# stwin_inclinometer.net
KiCad netlist of a schematic drawn in EAGLE
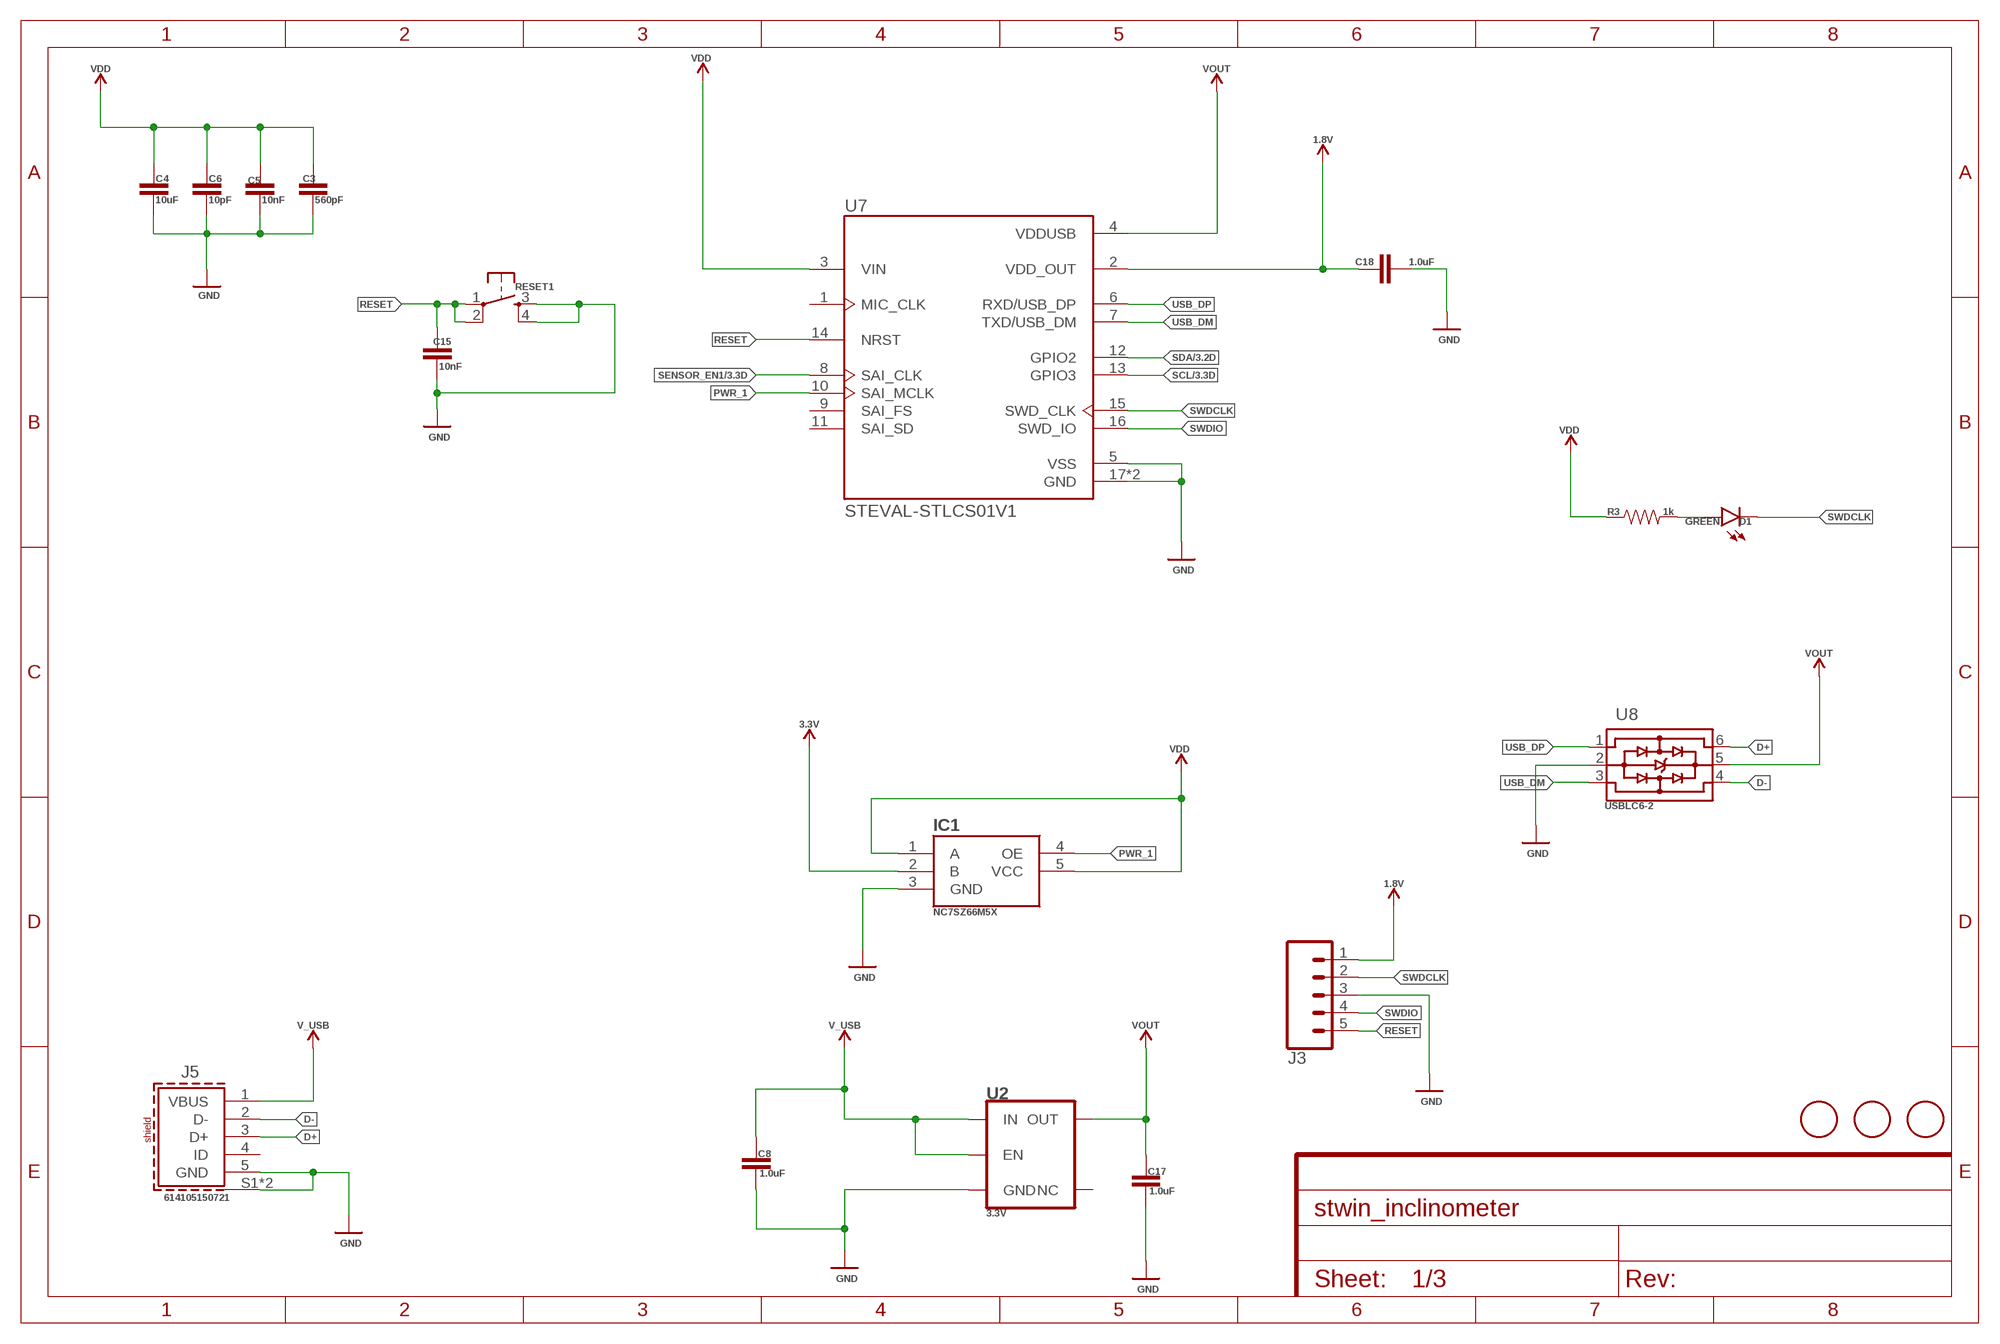
[diagram p0: schematic, sheet 1]
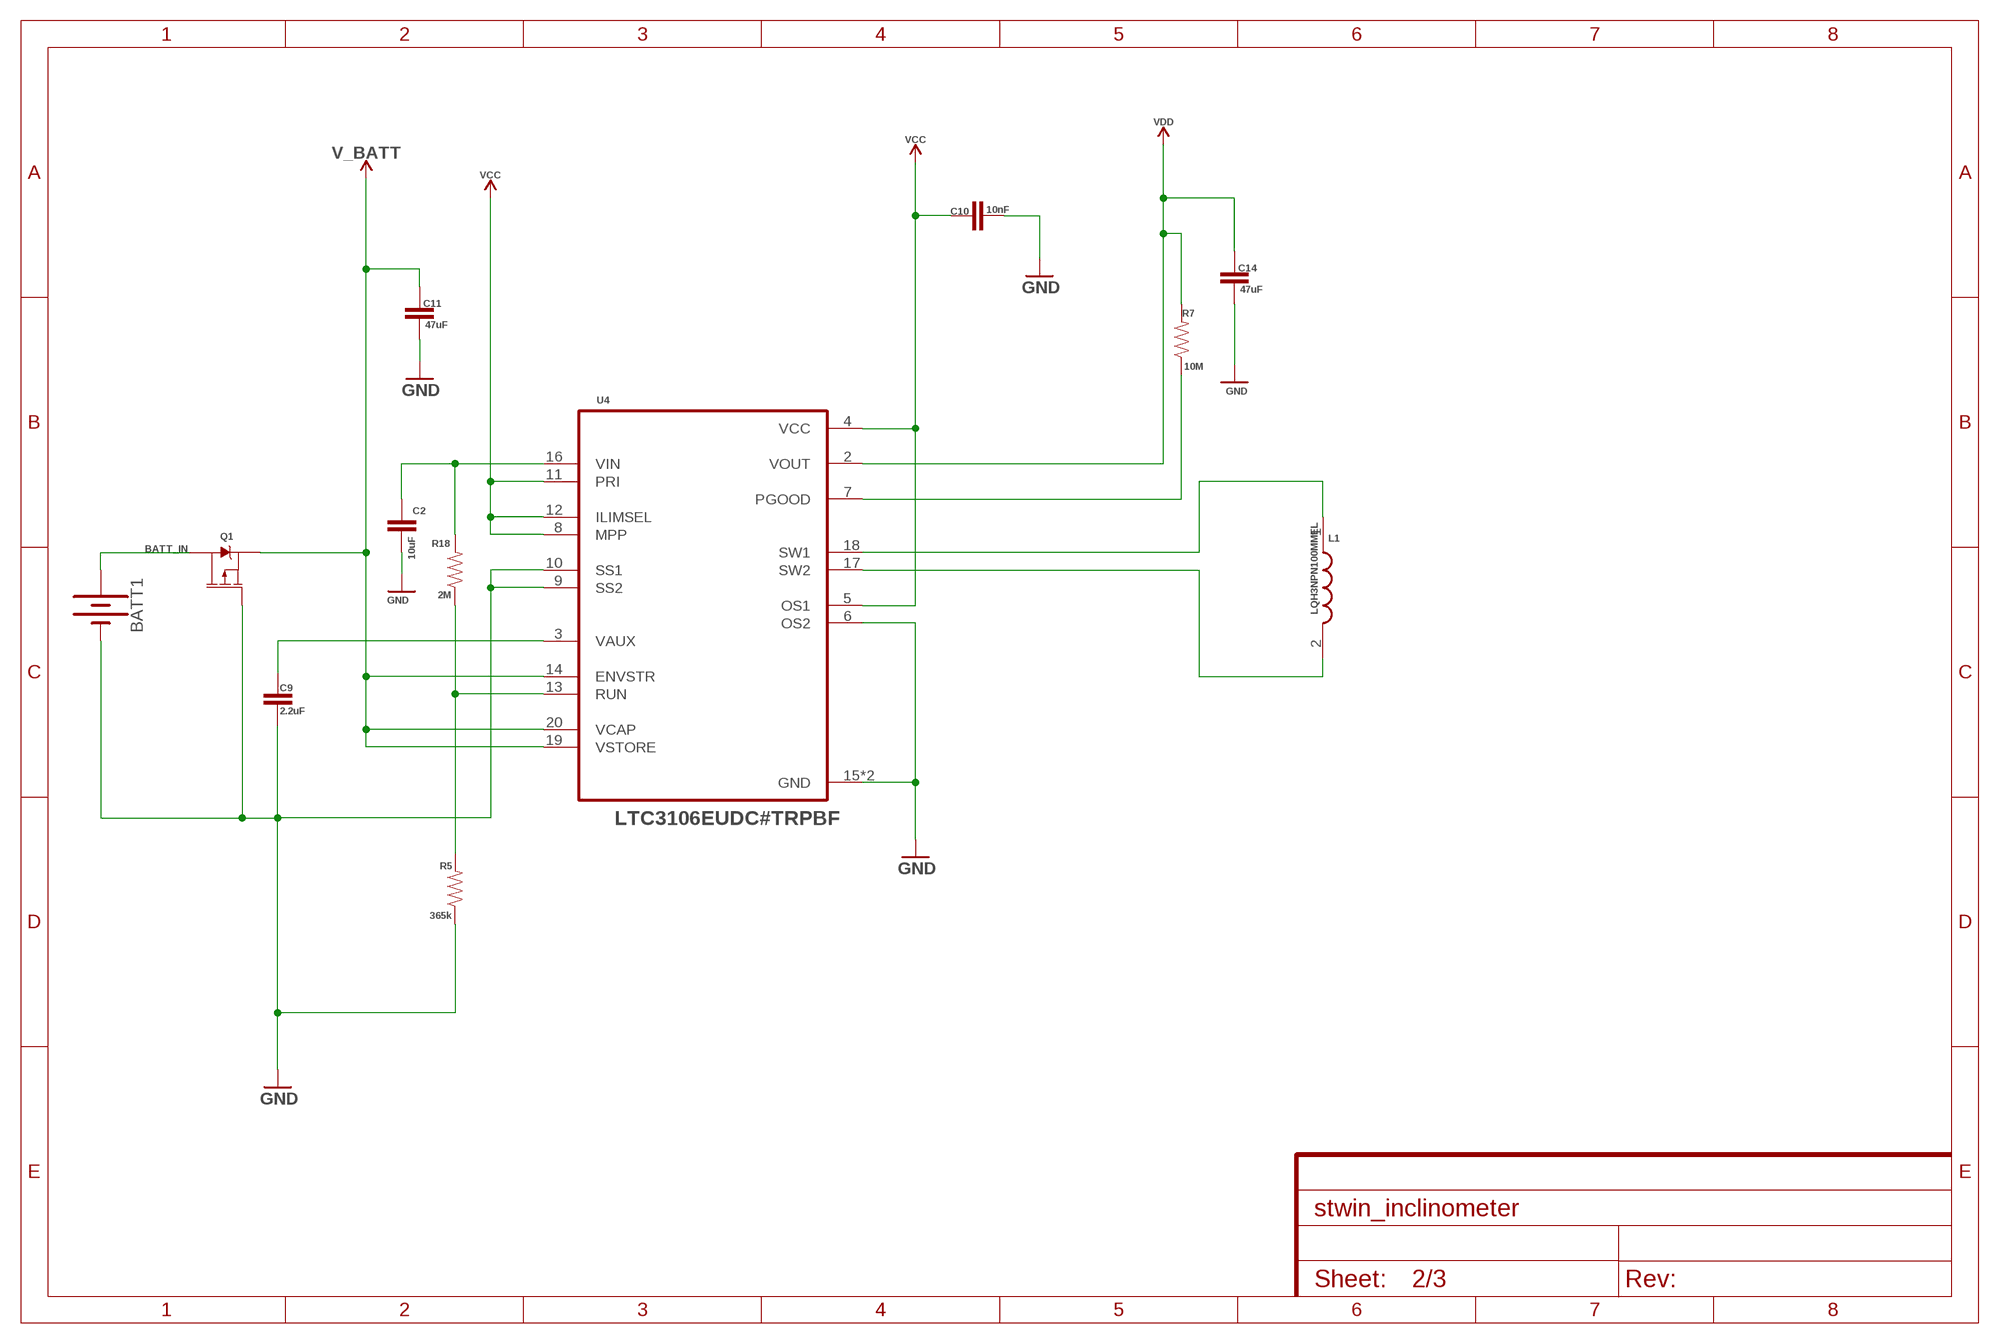
[diagram p1: schematic, sheet 2]
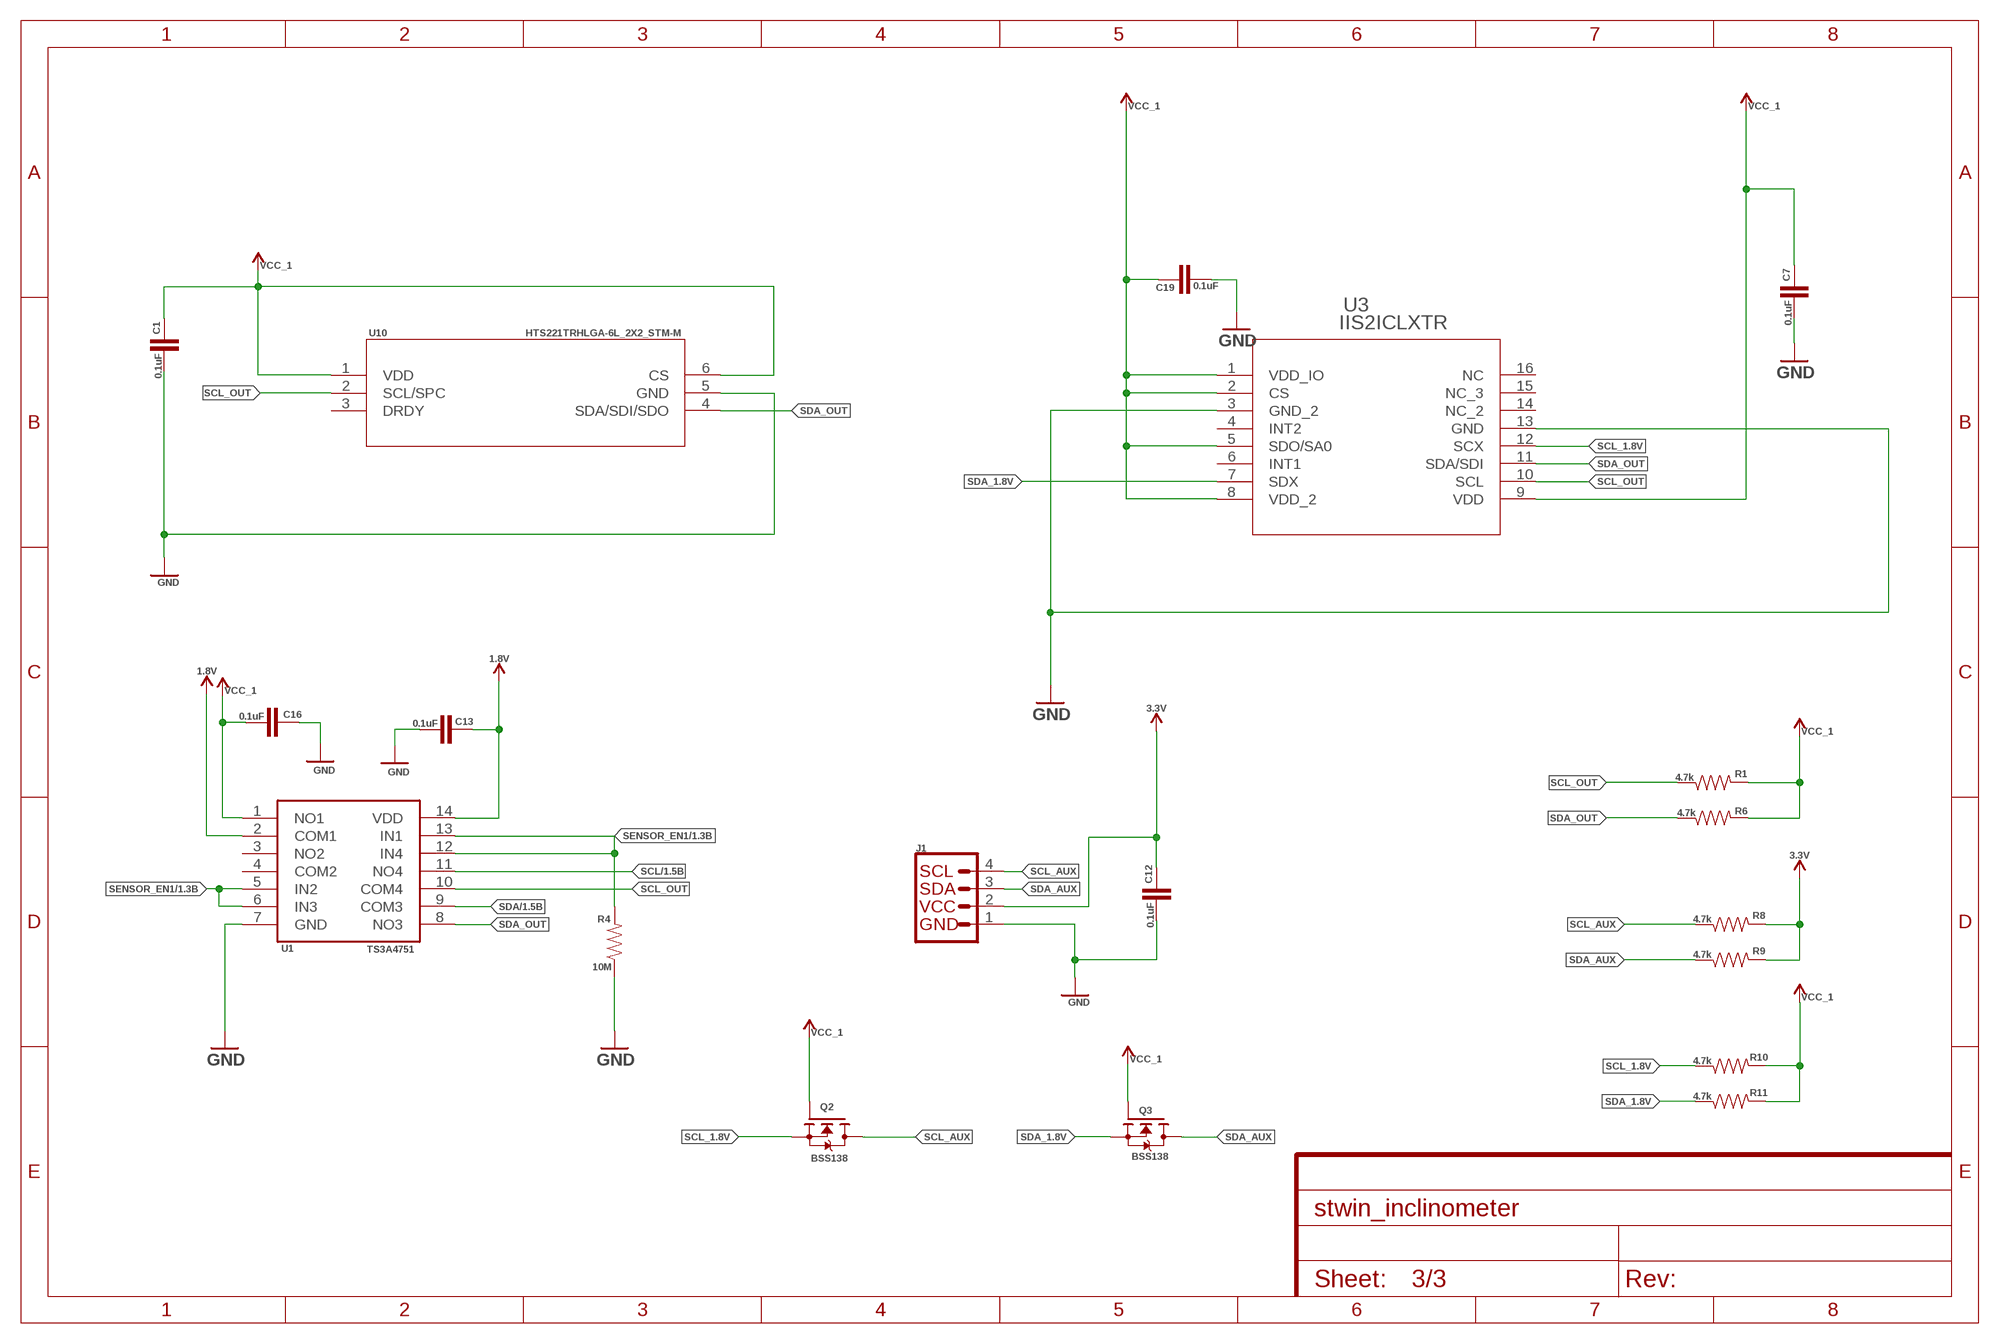
[diagram p2: schematic, sheet 3]

(export (version "E")
  (design (tool "Eeschema 10.0.6"))
  (components
    (comp (ref "C1")
      (value "0.1uF")
      (footprint "eagle-import:0603")
      (libsource (lib "eagle-import") (part "0.1UF-0603-25V-(+80/-20%)"))
    )
    (comp (ref "C7")
      (value "0.1uF")
      (footprint "eagle-import:0603")
      (libsource (lib "eagle-import") (part "0.1UF-0603-25V-(+80/-20%)"))
    )
    (comp (ref "C12")
      (value "0.1uF")
      (footprint "eagle-import:0603")
      (libsource (lib "eagle-import") (part "0.1UF-0603-25V-(+80/-20%)"))
    )
    (comp (ref "C13")
      (value "0.1uF")
      (footprint "eagle-import:0603")
      (libsource (lib "eagle-import") (part "0.1UF-0603-25V-(+80/-20%)"))
    )
    (comp (ref "C16")
      (value "0.1uF")
      (footprint "eagle-import:0603")
      (libsource (lib "eagle-import") (part "0.1UF-0603-25V-(+80/-20%)"))
    )
    (comp (ref "C19")
      (value "0.1uF")
      (footprint "eagle-import:0603")
      (libsource (lib "eagle-import") (part "0.1UF-0603-25V-(+80/-20%)"))
    )
    (comp (ref "J1")
      (value "I2C_STANDARD")
      (footprint "eagle-import:1X04")
      (libsource (lib "eagle-import") (part "I2C_STANDARD"))
    )
    (comp (ref "Q2")
      (value "BSS138")
      (footprint "eagle-import:SOT95P240X111-3N")
      (fields (field (name "MF") "ON Semiconductor"))
      (libsource (lib "eagle-import") (part "BSS138"))
    )
    (comp (ref "Q3")
      (value "BSS138")
      (footprint "eagle-import:SOT95P240X111-3N")
      (fields (field (name "MF") "ON Semiconductor"))
      (libsource (lib "eagle-import") (part "BSS138"))
    )
    (comp (ref "R1")
      (value "4.7k")
      (footprint "eagle-import:0603")
      (libsource (lib "eagle-import") (part "4.7KOHM-0603-1/10W-1%"))
    )
    (comp (ref "R4")
      (value "10M")
      (footprint "eagle-import:0603")
      (libsource (lib "eagle-import") (part "10MOHM-0603-1/10W-5%"))
    )
    (comp (ref "R6")
      (value "4.7k")
      (footprint "eagle-import:0603")
      (libsource (lib "eagle-import") (part "4.7KOHM-0603-1/10W-1%"))
    )
    (comp (ref "R8")
      (value "4.7k")
      (footprint "eagle-import:0603")
      (libsource (lib "eagle-import") (part "4.7KOHM-0603-1/10W-1%"))
    )
    (comp (ref "R9")
      (value "4.7k")
      (footprint "eagle-import:0603")
      (libsource (lib "eagle-import") (part "4.7KOHM-0603-1/10W-1%"))
    )
    (comp (ref "R10")
      (value "4.7k")
      (footprint "eagle-import:0603")
      (libsource (lib "eagle-import") (part "4.7KOHM-0603-1/10W-1%"))
    )
    (comp (ref "R11")
      (value "4.7k")
      (footprint "eagle-import:0603")
      (libsource (lib "eagle-import") (part "4.7KOHM-0603-1/10W-1%"))
    )
    (comp (ref "U1")
      (value "TS3A4751")
      (footprint "eagle-import:14_PIN")
      (fields (field (name "MF") "Texas Instruments"))
      (libsource (lib "eagle-import") (part "TS3A4751"))
    )
    (comp (ref "U3")
      (value "IIS2ICLXTR")
      (footprint "eagle-import:QFN_ICLX_STM")
      (fields (field (name "COPYRIGHT") "Copyright (C) 2018 Accelerated Designs. All rights reserved"))
      (libsource (lib "eagle-import") (part "IIS2ICLXTR"))
    )
    (comp (ref "U10")
      (value "HTS221TRHLGA-6L_2X2_STM-M")
      (footprint "eagle-import:HLGA-6L_2X2_STM-M")
      (fields
        (field (name "MANUFACTURER_PART_NUMBER") "HTS221TR")
        (field (name "COPYRIGHT") "Copyright (C) 2018 Accelerated Designs. All rights reserved")
      )
      (libsource (lib "eagle-import") (part "HTS221TRHLGA-6L_2X2_STM-M"))
    )
    (comp (ref "C3")
      (value "560pF")
      (footprint "eagle-import:0603")
      (libsource (lib "eagle-import") (part "560PF-0603-50V-5%"))
    )
    (comp (ref "C4")
      (value "10uF")
      (footprint "eagle-import:0603")
      (libsource (lib "eagle-import") (part "10UF-0603-6.3V-20%"))
    )
    (comp (ref "C5")
      (value "10nF")
      (footprint "eagle-import:0603")
      (libsource (lib "eagle-import") (part "10NF-0603-50V-10%"))
    )
    (comp (ref "C6")
      (value "10pF")
      (footprint "eagle-import:0603")
      (libsource (lib "eagle-import") (part "10PF-0603-50V-5%"))
    )
    (comp (ref "C8")
      (value "1.0uF")
      (footprint "eagle-import:0603")
      (libsource (lib "eagle-import") (part "1.0UF-0603-16V-10%"))
    )
    (comp (ref "C15")
      (value "10nF")
      (footprint "eagle-import:0603")
      (libsource (lib "eagle-import") (part "10NF-0603-50V-10%"))
    )
    (comp (ref "C17")
      (value "1.0uF")
      (footprint "eagle-import:0603")
      (libsource (lib "eagle-import") (part "1.0UF-0603-16V-10%"))
    )
    (comp (ref "C18")
      (value "1.0uF")
      (footprint "eagle-import:0603")
      (libsource (lib "eagle-import") (part "1.0UF-0603-16V-10%"))
    )
    (comp (ref "D1")
      (value "GREEN")
      (footprint "eagle-import:LED-0603")
      (libsource (lib "eagle-import") (part "LED-GREEN0603"))
    )
    (comp (ref "IC1")
      (value "NC7SZ66M5X")
      (footprint "eagle-import:SOT95P280X145-5N")
      (fields (field (name "MOUSER_PART_NUMBER") "512-NC7SZ66M5X"))
      (libsource (lib "eagle-import") (part "NC7SZ66M5X"))
    )
    (comp (ref "J3")
      (value "CONN_05LOCK_LONGPADS")
      (footprint "eagle-import:1X05_LOCK_LONGPADS")
      (libsource (lib "eagle-import") (part "CONN_05LOCK_LONGPADS"))
    )
    (comp (ref "J5")
      (value "614105150721")
      (footprint "eagle-import:614105150721")
      (fields (field (name "MF") "Wurth Electronics"))
      (libsource (lib "eagle-import") (part "614105150721"))
    )
    (comp (ref "R3")
      (value "1k")
      (footprint "eagle-import:0603")
      (libsource (lib "eagle-import") (part "1KOHM-0603-1/10W-1%"))
    )
    (comp (ref "RESET1")
      (value "MOMENTARY-SWITCH-SPST-2-SMD-4.6X2.8MM")
      (footprint "eagle-import:TACTILE_SWITCH_SMD_4.6X2.8MM")
      (libsource (lib "eagle-import") (part "MOMENTARY-SWITCH-SPST-2-SMD-4.6X2.8MM"))
    )
    (comp (ref "U$5")
      (value "FIDUCIAL")
      (footprint "eagle-import:FIDUCIAL_1MM")
      (libsource (lib "eagle-import") (part "FIDUCIAL"))
    )
    (comp (ref "U$6")
      (value "FIDUCIAL")
      (footprint "eagle-import:FIDUCIAL_1MM")
      (libsource (lib "eagle-import") (part "FIDUCIAL"))
    )
    (comp (ref "U$7")
      (value "FIDUCIAL")
      (footprint "eagle-import:FIDUCIAL_1MM")
      (libsource (lib "eagle-import") (part "FIDUCIAL"))
    )
    (comp (ref "U2")
      (value "3.3V")
      (footprint "eagle-import:SOT23-5")
      (libsource (lib "eagle-import") (part "V_REG_AP2112K-3.3V"))
    )
    (comp (ref "U7")
      (value "STEVAL-STLCS01V1")
      (footprint "eagle-import:XDCR_STEVAL-STLCS01V1")
      (fields (field (name "MF") "STMicroelectronics"))
      (libsource (lib "eagle-import") (part "STEVAL-STLCS01V1"))
    )
    (comp (ref "U8")
      (value "USBLC6-2")
      (footprint "eagle-import:USBLC6-2P6")
      (fields (field (name "MF") "STMicroelectronics"))
      (libsource (lib "eagle-import") (part "USBLC6-2"))
    )
    (comp (ref "BATT1")
      (value "KEYSTONE_54KEYSTONE_2")
      (footprint "eagle-import:KEYSTONE_V2")
      (libsource (lib "eagle-import") (part "KEYSTONE_54KEYSTONE_2"))
    )
    (comp (ref "C2")
      (value "10uF")
      (footprint "eagle-import:0603")
      (libsource (lib "eagle-import") (part "10UF-0603-6.3V-20%"))
    )
    (comp (ref "C9")
      (value "2.2uF")
      (footprint "eagle-import:0603")
      (libsource (lib "eagle-import") (part "2.2UF-0603-10V-20%"))
    )
    (comp (ref "C10")
      (value "10nF")
      (footprint "eagle-import:0603")
      (libsource (lib "eagle-import") (part "10NF-0603-50V-10%"))
    )
    (comp (ref "C11")
      (value "47uF")
      (footprint "eagle-import:0603")
      (libsource (lib "eagle-import") (part "4.7UF0603"))
    )
    (comp (ref "C14")
      (value "47uF")
      (footprint "eagle-import:0603")
      (libsource (lib "eagle-import") (part "4.7UF0603"))
    )
    (comp (ref "L1")
      (value "LQH3NPN100MMEL")
      (footprint "eagle-import:INDPM3030X150N")
      (fields (field (name "MOUSER_PART_NUMBER") "81-LQH3NPN100MMEL"))
      (libsource (lib "eagle-import") (part "LQH3NPN100MMEL"))
    )
    (comp (ref "Q1")
      (value "2.5A/30V/105mΩ")
      (footprint "eagle-import:SOT23-3")
      (libsource (lib "eagle-import") (part "MOSFET_PCH-DMG2307L"))
    )
    (comp (ref "R5")
      (value "365k")
      (footprint "eagle-import:0603")
      (libsource (lib "eagle-import") (part "348KOHM-0603-1/10W-1%"))
    )
    (comp (ref "R7")
      (value "10M")
      (footprint "eagle-import:0603")
      (libsource (lib "eagle-import") (part "10MOHM-0603-1/10W-5%"))
    )
    (comp (ref "R18")
      (value "2M")
      (footprint "eagle-import:0603")
      (libsource (lib "eagle-import") (part "1MOHM-0603-1/4W-5%"))
    )
    (comp (ref "U4")
      (value "LTC3106EUDC#TRPBF")
      (footprint "eagle-import:QFN50P400X300X80-21N")
      (fields (field (name "MF") "Linear Technology/Analog"))
      (libsource (lib "eagle-import") (part "LTC3106EUDC#TRPBF"))
    )
  )
  (nets
    (net (code "1") (name "1.8V") (class "Default")
      (node (ref "C13") (pin "1") (pinfunction "1_1") (pintype "passive"))
      (node (ref "C18") (pin "1") (pinfunction "1_1") (pintype "passive"))
      (node (ref "J3") (pin "1") (pinfunction "1_1") (pintype "passive"))
      (node (ref "U1") (pin "14") (pinfunction "VDD_14") (pintype "bidirectional"))
      (node (ref "U1") (pin "2") (pinfunction "COM1_2") (pintype "bidirectional"))
      (node (ref "U7") (pin "2") (pinfunction "VDD_OUT_2") (pintype "output"))
    )
    (net (code "2") (name "3.3V") (class "Default")
      (node (ref "C12") (pin "1") (pinfunction "1_1") (pintype "passive"))
      (node (ref "IC1") (pin "2") (pinfunction "B_2") (pintype "bidirectional"))
      (node (ref "J1") (pin "2") (pinfunction "2_2") (pintype "power_in"))
      (node (ref "R8") (pin "2") (pinfunction "2_2") (pintype "passive"))
      (node (ref "R9") (pin "2") (pinfunction "2_2") (pintype "passive"))
    )
    (net (code "3") (name "BATT_IN") (class "Default")
      (node (ref "BATT1") (pin "P$1") (pinfunction "+_P$1") (pintype "power_in"))
      (node (ref "BATT1") (pin "P$2") (pinfunction "+_P$2") (pintype "power_in"))
      (node (ref "BATT1") (pin "P$3") (pinfunction "+_P$3") (pintype "power_in"))
      (node (ref "Q1") (pin "3") (pinfunction "D_3") (pintype "bidirectional"))
    )
    (net (code "4") (name "D+") (class "Default")
      (node (ref "J5") (pin "3") (pinfunction "D+_3") (pintype "passive"))
      (node (ref "U8") (pin "6") (pinfunction "6_6") (pintype "bidirectional"))
    )
    (net (code "5") (name "D-") (class "Default")
      (node (ref "J5") (pin "2") (pinfunction "D-_2") (pintype "passive"))
      (node (ref "U8") (pin "4") (pinfunction "4_4") (pintype "bidirectional"))
    )
    (net (code "6") (name "GND") (class "Default")
      (node (ref "BATT1") (pin "P$4") (pinfunction "-_P$4") (pintype "power_in"))
      (node (ref "BATT1") (pin "P$5") (pinfunction "-_P$5") (pintype "power_in"))
      (node (ref "BATT1") (pin "P$6") (pinfunction "-_P$6") (pintype "power_in"))
      (node (ref "C1") (pin "2") (pinfunction "2_2") (pintype "passive"))
      (node (ref "C10") (pin "2") (pinfunction "2_2") (pintype "passive"))
      (node (ref "C11") (pin "2") (pinfunction "2_2") (pintype "passive"))
      (node (ref "C12") (pin "2") (pinfunction "2_2") (pintype "passive"))
      (node (ref "C13") (pin "2") (pinfunction "2_2") (pintype "passive"))
      (node (ref "C14") (pin "2") (pinfunction "2_2") (pintype "passive"))
      (node (ref "C15") (pin "1") (pinfunction "1_1") (pintype "passive"))
      (node (ref "C16") (pin "1") (pinfunction "1_1") (pintype "passive"))
      (node (ref "C17") (pin "2") (pinfunction "2_2") (pintype "passive"))
      (node (ref "C18") (pin "2") (pinfunction "2_2") (pintype "passive"))
      (node (ref "C19") (pin "2") (pinfunction "2_2") (pintype "passive"))
      (node (ref "C2") (pin "2") (pinfunction "2_2") (pintype "passive"))
      (node (ref "C3") (pin "1") (pinfunction "1_1") (pintype "passive"))
      (node (ref "C4") (pin "1") (pinfunction "1_1") (pintype "passive"))
      (node (ref "C5") (pin "1") (pinfunction "1_1") (pintype "passive"))
      (node (ref "C6") (pin "1") (pinfunction "1_1") (pintype "passive"))
      (node (ref "C7") (pin "2") (pinfunction "2_2") (pintype "passive"))
      (node (ref "C8") (pin "2") (pinfunction "2_2") (pintype "passive"))
      (node (ref "C9") (pin "2") (pinfunction "2_2") (pintype "passive"))
      (node (ref "IC1") (pin "3") (pinfunction "GND_3") (pintype "power_in"))
      (node (ref "J1") (pin "1") (pinfunction "1_1") (pintype "power_in"))
      (node (ref "J3") (pin "3") (pinfunction "3_3") (pintype "passive"))
      (node (ref "J5") (pin "5") (pinfunction "GND_5") (pintype "passive"))
      (node (ref "J5") (pin "S1") (pinfunction "SHIELD_S1") (pintype "passive"))
      (node (ref "J5") (pin "S2") (pinfunction "SHIELD_S2") (pintype "passive"))
      (node (ref "Q1") (pin "1") (pinfunction "G_1") (pintype "bidirectional"))
      (node (ref "R4") (pin "1") (pinfunction "1_1") (pintype "passive"))
      (node (ref "R5") (pin "1") (pinfunction "1_1") (pintype "passive"))
      (node (ref "RESET1") (pin "3") (pinfunction "3_3") (pintype "passive"))
      (node (ref "RESET1") (pin "4") (pinfunction "4_4") (pintype "passive"))
      (node (ref "U1") (pin "7") (pinfunction "GND_7") (pintype "bidirectional"))
      (node (ref "U10") (pin "5") (pinfunction "GND_5") (pintype "passive"))
      (node (ref "U2") (pin "2") (pinfunction "GND_2") (pintype "input"))
      (node (ref "U3") (pin "13") (pinfunction "GND_13") (pintype "passive"))
      (node (ref "U3") (pin "3") (pinfunction "GND_2_3") (pintype "passive"))
      (node (ref "U4") (pin "10") (pinfunction "SS1_10") (pintype "input"))
      (node (ref "U4") (pin "15") (pinfunction "GND_15") (pintype "power_in"))
      (node (ref "U4") (pin "21") (pinfunction "GND_21") (pintype "power_in"))
      (node (ref "U4") (pin "6") (pinfunction "OS2_6") (pintype "input"))
      (node (ref "U4") (pin "9") (pinfunction "SS2_9") (pintype "input"))
      (node (ref "U7") (pin "17") (pinfunction "GND_17") (pintype "power_in"))
      (node (ref "U7") (pin "18") (pinfunction "GND_18") (pintype "power_in"))
      (node (ref "U7") (pin "5") (pinfunction "VSS_5") (pintype "power_in"))
      (node (ref "U8") (pin "2") (pinfunction "2_2") (pintype "power_in"))
    )
    (net (code "7") (name "Net-(D1-PadA)") (class "Default")
      (node (ref "D1") (pin "A") (pinfunction "A_A") (pintype "passive"))
      (node (ref "R3") (pin "2") (pinfunction "2_2") (pintype "passive"))
    )
    (net (code "8") (name "Net-(U4-PGOOD)") (class "Default")
      (node (ref "R7") (pin "1") (pinfunction "1_1") (pintype "passive"))
      (node (ref "U4") (pin "7") (pinfunction "PGOOD_7") (pintype "bidirectional"))
    )
    (net (code "9") (name "Net-(U4-RUN)") (class "Default")
      (node (ref "R18") (pin "1") (pinfunction "1_1") (pintype "passive"))
      (node (ref "R5") (pin "2") (pinfunction "2_2") (pintype "passive"))
      (node (ref "U4") (pin "13") (pinfunction "RUN_13") (pintype "input"))
    )
    (net (code "10") (name "Net-(U4-SW1)") (class "Default")
      (node (ref "L1") (pin "1") (pinfunction "1_1") (pintype "bidirectional"))
      (node (ref "U4") (pin "18") (pinfunction "SW1_18") (pintype "bidirectional"))
    )
    (net (code "11") (name "Net-(U4-SW2)") (class "Default")
      (node (ref "L1") (pin "2") (pinfunction "2_2") (pintype "bidirectional"))
      (node (ref "U4") (pin "17") (pinfunction "SW2_17") (pintype "bidirectional"))
    )
    (net (code "12") (name "Net-(U4-VAUX)") (class "Default")
      (node (ref "C9") (pin "1") (pinfunction "1_1") (pintype "passive"))
      (node (ref "U4") (pin "3") (pinfunction "VAUX_3") (pintype "bidirectional"))
    )
    (net (code "13") (name "Net-(U4-VIN)") (class "Default")
      (node (ref "C2") (pin "1") (pinfunction "1_1") (pintype "passive"))
      (node (ref "R18") (pin "2") (pinfunction "2_2") (pintype "passive"))
      (node (ref "U4") (pin "16") (pinfunction "VIN_16") (pintype "input"))
    )
    (net (code "14") (name "PWR_1") (class "Default")
      (node (ref "IC1") (pin "4") (pinfunction "OE_4") (pintype "input"))
      (node (ref "U7") (pin "10") (pinfunction "SAI_MCLK_10") (pintype "bidirectional"))
    )
    (net (code "15") (name "RESET") (class "Default")
      (node (ref "C15") (pin "2") (pinfunction "2_2") (pintype "passive"))
      (node (ref "J3") (pin "5") (pinfunction "5_5") (pintype "passive"))
      (node (ref "RESET1") (pin "1") (pinfunction "1_1") (pintype "passive"))
      (node (ref "RESET1") (pin "2") (pinfunction "2_2") (pintype "passive"))
      (node (ref "U7") (pin "14") (pinfunction "NRST_14") (pintype "input"))
    )
    (net (code "16") (name "SCL") (class "Default")
      (node (ref "U1") (pin "11") (pinfunction "NO4_11") (pintype "bidirectional"))
      (node (ref "U7") (pin "13") (pinfunction "GPIO3_13") (pintype "bidirectional"))
    )
    (net (code "17") (name "SCL_1.8V") (class "Default")
      (node (ref "Q2") (pin "2") (pinfunction "S_2") (pintype "passive"))
      (node (ref "R10") (pin "1") (pinfunction "1_1") (pintype "passive"))
      (node (ref "U3") (pin "12") (pinfunction "SCX_12") (pintype "passive"))
    )
    (net (code "18") (name "SCL_AUX") (class "Default")
      (node (ref "J1") (pin "4") (pinfunction "4_4") (pintype "passive"))
      (node (ref "Q2") (pin "3") (pinfunction "D_3") (pintype "passive"))
      (node (ref "R8") (pin "1") (pinfunction "1_1") (pintype "passive"))
    )
    (net (code "19") (name "SCL_OUT") (class "Default")
      (node (ref "R1") (pin "1") (pinfunction "1_1") (pintype "passive"))
      (node (ref "U1") (pin "10") (pinfunction "COM4_10") (pintype "bidirectional"))
      (node (ref "U10") (pin "2") (pinfunction "SCL/SPC_2") (pintype "passive"))
      (node (ref "U3") (pin "10") (pinfunction "SCL_10") (pintype "passive"))
    )
    (net (code "20") (name "SDA") (class "Default")
      (node (ref "U1") (pin "9") (pinfunction "COM3_9") (pintype "bidirectional"))
      (node (ref "U7") (pin "12") (pinfunction "GPIO2_12") (pintype "bidirectional"))
    )
    (net (code "21") (name "SDA_1.8V") (class "Default")
      (node (ref "Q3") (pin "2") (pinfunction "S_2") (pintype "passive"))
      (node (ref "R11") (pin "1") (pinfunction "1_1") (pintype "passive"))
      (node (ref "U3") (pin "7") (pinfunction "SDX_7") (pintype "passive"))
    )
    (net (code "22") (name "SDA_AUX") (class "Default")
      (node (ref "J1") (pin "3") (pinfunction "3_3") (pintype "passive"))
      (node (ref "Q3") (pin "3") (pinfunction "D_3") (pintype "passive"))
      (node (ref "R9") (pin "1") (pinfunction "1_1") (pintype "passive"))
    )
    (net (code "23") (name "SDA_OUT") (class "Default")
      (node (ref "R6") (pin "1") (pinfunction "1_1") (pintype "passive"))
      (node (ref "U1") (pin "8") (pinfunction "NO3_8") (pintype "bidirectional"))
      (node (ref "U10") (pin "4") (pinfunction "SDA/SDI/SDO_4") (pintype "passive"))
      (node (ref "U3") (pin "11") (pinfunction "SDA/SDI_11") (pintype "passive"))
    )
    (net (code "24") (name "SENSOR_EN1") (class "Default")
      (node (ref "R4") (pin "2") (pinfunction "2_2") (pintype "passive"))
      (node (ref "U1") (pin "12") (pinfunction "IN4_12") (pintype "bidirectional"))
      (node (ref "U1") (pin "13") (pinfunction "IN1_13") (pintype "bidirectional"))
      (node (ref "U1") (pin "5") (pinfunction "IN2_5") (pintype "bidirectional"))
      (node (ref "U1") (pin "6") (pinfunction "IN3_6") (pintype "bidirectional"))
      (node (ref "U7") (pin "8") (pinfunction "SAI_CLK_8") (pintype "bidirectional"))
    )
    (net (code "25") (name "SWDCLK") (class "Default")
      (node (ref "D1") (pin "C") (pinfunction "C_C") (pintype "passive"))
      (node (ref "J3") (pin "2") (pinfunction "2_2") (pintype "passive"))
      (node (ref "U7") (pin "15") (pinfunction "SWD_CLK_15") (pintype "bidirectional"))
    )
    (net (code "26") (name "SWDIO") (class "Default")
      (node (ref "J3") (pin "4") (pinfunction "4_4") (pintype "passive"))
      (node (ref "U7") (pin "16") (pinfunction "SWD_IO_16") (pintype "bidirectional"))
    )
    (net (code "27") (name "USB_DM") (class "Default")
      (node (ref "U7") (pin "7") (pinfunction "TXD/USB_DM_7") (pintype "bidirectional"))
      (node (ref "U8") (pin "3") (pinfunction "3_3") (pintype "bidirectional"))
    )
    (net (code "28") (name "USB_DP") (class "Default")
      (node (ref "U7") (pin "6") (pinfunction "RXD/USB_DP_6") (pintype "bidirectional"))
      (node (ref "U8") (pin "1") (pinfunction "1_1") (pintype "bidirectional"))
    )
    (net (code "29") (name "VCC") (class "Default")
      (node (ref "C10") (pin "1") (pinfunction "1_1") (pintype "passive"))
      (node (ref "U4") (pin "11") (pinfunction "PRI_11") (pintype "input"))
      (node (ref "U4") (pin "12") (pinfunction "ILIMSEL_12") (pintype "input"))
      (node (ref "U4") (pin "4") (pinfunction "VCC_4") (pintype "power_in"))
      (node (ref "U4") (pin "5") (pinfunction "OS1_5") (pintype "input"))
      (node (ref "U4") (pin "8") (pinfunction "MPP_8") (pintype "input"))
    )
    (net (code "30") (name "VCC_1") (class "Default")
      (node (ref "C1") (pin "1") (pinfunction "1_1") (pintype "passive"))
      (node (ref "C16") (pin "2") (pinfunction "2_2") (pintype "passive"))
      (node (ref "C19") (pin "1") (pinfunction "1_1") (pintype "passive"))
      (node (ref "C7") (pin "1") (pinfunction "1_1") (pintype "passive"))
      (node (ref "Q2") (pin "1") (pinfunction "G_1") (pintype "passive"))
      (node (ref "Q3") (pin "1") (pinfunction "G_1") (pintype "passive"))
      (node (ref "R1") (pin "2") (pinfunction "2_2") (pintype "passive"))
      (node (ref "R10") (pin "2") (pinfunction "2_2") (pintype "passive"))
      (node (ref "R11") (pin "2") (pinfunction "2_2") (pintype "passive"))
      (node (ref "R6") (pin "2") (pinfunction "2_2") (pintype "passive"))
      (node (ref "U1") (pin "1") (pinfunction "NO1_1") (pintype "bidirectional"))
      (node (ref "U10") (pin "1") (pinfunction "VDD_1") (pintype "power_in"))
      (node (ref "U10") (pin "6") (pinfunction "CS_6") (pintype "passive"))
      (node (ref "U3") (pin "1") (pinfunction "VDD_IO_1") (pintype "power_in"))
      (node (ref "U3") (pin "2") (pinfunction "CS_2") (pintype "passive"))
      (node (ref "U3") (pin "5") (pinfunction "SDO/SA0_5") (pintype "passive"))
      (node (ref "U3") (pin "8") (pinfunction "VDD_2_8") (pintype "power_in"))
      (node (ref "U3") (pin "9") (pinfunction "VDD_9") (pintype "power_in"))
    )
    (net (code "31") (name "VDD") (class "Default")
      (node (ref "C14") (pin "1") (pinfunction "1_1") (pintype "passive"))
      (node (ref "C3") (pin "2") (pinfunction "2_2") (pintype "passive"))
      (node (ref "C4") (pin "2") (pinfunction "2_2") (pintype "passive"))
      (node (ref "C5") (pin "2") (pinfunction "2_2") (pintype "passive"))
      (node (ref "C6") (pin "2") (pinfunction "2_2") (pintype "passive"))
      (node (ref "IC1") (pin "1") (pinfunction "A_1") (pintype "bidirectional"))
      (node (ref "IC1") (pin "5") (pinfunction "VCC_5") (pintype "power_in"))
      (node (ref "R3") (pin "1") (pinfunction "1_1") (pintype "passive"))
      (node (ref "R7") (pin "2") (pinfunction "2_2") (pintype "passive"))
      (node (ref "U4") (pin "2") (pinfunction "VOUT_2") (pintype "output"))
      (node (ref "U7") (pin "3") (pinfunction "VIN_3") (pintype "input"))
    )
    (net (code "32") (name "VOUT") (class "Default")
      (node (ref "C17") (pin "1") (pinfunction "1_1") (pintype "passive"))
      (node (ref "U2") (pin "5") (pinfunction "OUT_5") (pintype "passive"))
      (node (ref "U7") (pin "4") (pinfunction "VDDUSB_4") (pintype "power_in"))
      (node (ref "U8") (pin "5") (pinfunction "5_5") (pintype "power_in"))
    )
    (net (code "33") (name "V_BATT") (class "Default")
      (node (ref "C11") (pin "1") (pinfunction "1_1") (pintype "passive"))
      (node (ref "Q1") (pin "2") (pinfunction "S_2") (pintype "bidirectional"))
      (node (ref "U4") (pin "14") (pinfunction "ENVSTR_14") (pintype "input"))
      (node (ref "U4") (pin "19") (pinfunction "VSTORE_19") (pintype "bidirectional"))
      (node (ref "U4") (pin "20") (pinfunction "VCAP_20") (pintype "bidirectional"))
    )
    (net (code "34") (name "V_USB") (class "Default")
      (node (ref "C8") (pin "1") (pinfunction "1_1") (pintype "passive"))
      (node (ref "J5") (pin "1") (pinfunction "VBUS_1") (pintype "passive"))
      (node (ref "U2") (pin "1") (pinfunction "IN_1") (pintype "input"))
      (node (ref "U2") (pin "3") (pinfunction "EN_3") (pintype "input"))
    )
    (net (code "35") (name "unconnected-(J5-ID-Pad4)") (class "Default")
      (node (ref "J5") (pin "4") (pinfunction "ID_4") (pintype "passive"))
    )
    (net (code "36") (name "unconnected-(U1-COM2-Pad4)") (class "Default")
      (node (ref "U1") (pin "4") (pinfunction "COM2_4") (pintype "bidirectional"))
    )
    (net (code "37") (name "unconnected-(U1-NO2-Pad3)") (class "Default")
      (node (ref "U1") (pin "3") (pinfunction "NO2_3") (pintype "bidirectional"))
    )
    (net (code "38") (name "unconnected-(U2-NC-Pad4)") (class "Default")
      (node (ref "U2") (pin "4") (pinfunction "NC_4") (pintype "no_connect"))
    )
    (net (code "39") (name "unconnected-(U3-INT1-Pad6)") (class "Default")
      (node (ref "U3") (pin "6") (pinfunction "INT1_6") (pintype "input"))
    )
    (net (code "40") (name "unconnected-(U3-INT2-Pad4)") (class "Default")
      (node (ref "U3") (pin "4") (pinfunction "INT2_4") (pintype "input"))
    )
    (net (code "41") (name "unconnected-(U3-NC-Pad16)") (class "Default")
      (node (ref "U3") (pin "16") (pinfunction "NC_16") (pintype "no_connect"))
    )
    (net (code "42") (name "unconnected-(U3-NC_2-Pad14)") (class "Default")
      (node (ref "U3") (pin "14") (pinfunction "NC_2_14") (pintype "no_connect"))
    )
    (net (code "43") (name "unconnected-(U3-NC_3-Pad15)") (class "Default")
      (node (ref "U3") (pin "15") (pinfunction "NC_3_15") (pintype "no_connect"))
    )
    (net (code "44") (name "unconnected-(U7-MIC_CLK-Pad1)") (class "Default")
      (node (ref "U7") (pin "1") (pinfunction "MIC_CLK_1") (pintype "input"))
    )
    (net (code "45") (name "unconnected-(U7-SAI_FS-Pad9)") (class "Default")
      (node (ref "U7") (pin "9") (pinfunction "SAI_FS_9") (pintype "bidirectional"))
    )
    (net (code "46") (name "unconnected-(U7-SAI_SD-Pad11)") (class "Default")
      (node (ref "U7") (pin "11") (pinfunction "SAI_SD_11") (pintype "bidirectional"))
    )
    (net (code "47") (name "unconnected-(U10-DRDY-Pad3)") (class "Default")
      (node (ref "U10") (pin "3") (pinfunction "DRDY_3") (pintype "passive"))
    )
  )
)
